# filter-10.net
KiCad netlist of a schematic drawn in Altium Designer
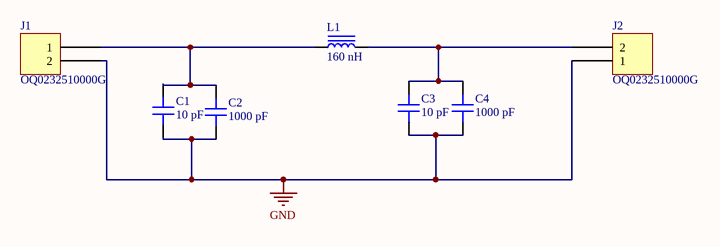
[diagram p0: filter-10.SchDoc]

(export (version "E")
  (design (tool "Eeschema 10.0.6"))
  (components
    (comp (ref "C1")
      (value "10 pF")
      (footprint "CAP 0603_1608")
      (description "CAP CER 10PF 100V C0G/NPO 0603")
      (fields (field (name "PART NUMBER") "AC0603JRNPO0BN100") (field (name "MANUFACTURER") "Yageo"))
      (libsource (lib "Celestial Altium Library - altium_library") (part "Capacitor"))
    )
    (comp (ref "C2")
      (value "1000 pF")
      (footprint "CAP 0603_1608")
      (description "CAP CER 1000PF 100V X7R 0603")
      (fields
        (field (name "PART NUMBER") "GCD188R72A102KA01D")
        (field (name "MANUFACTURER") "Murata Electronics")
      )
      (libsource (lib "Celestial Altium Library - altium_library") (part "Capacitor"))
    )
    (comp (ref "C3")
      (value "10 pF")
      (footprint "CAP 0603_1608")
      (description "CAP CER 10PF 100V C0G/NPO 0603")
      (fields (field (name "PART NUMBER") "AC0603JRNPO0BN100") (field (name "MANUFACTURER") "Yageo"))
      (libsource (lib "Celestial Altium Library - altium_library") (part "Capacitor"))
    )
    (comp (ref "C4")
      (value "1000 pF")
      (footprint "CAP 0603_1608")
      (description "CAP CER 1000PF 100V X7R 0603")
      (fields
        (field (name "PART NUMBER") "GCD188R72A102KA01D")
        (field (name "MANUFACTURER") "Murata Electronics")
      )
      (libsource (lib "Celestial Altium Library - altium_library") (part "Capacitor"))
    )
    (comp (ref "J1")
      (value "OQ0232510000G")
      (footprint "FCI 06-381-2PIN")
      (description "TERM BLOCK HDR 2POS 90DEG 3.81MM")
      (fields (field (name "MANUFACTURER") "Amphenol Anytek"))
      (libsource (lib "Celestial Altium Library - altium_library") (part "2 Pin"))
    )
    (comp (ref "J2")
      (value "OQ0232510000G")
      (footprint "FCI 06-381-2PIN")
      (description "TERM BLOCK HDR 2POS 90DEG 3.81MM")
      (fields (field (name "MANUFACTURER") "Amphenol Anytek"))
      (libsource (lib "") (part "2 Pin_1"))
    )
    (comp (ref "L1")
      (value "160 nH")
      (footprint "IND 0402_1005 RF WW")
      (description "FIXED IND 160NH 480MA 330MOHM SM")
      (fields
        (field (name "PART NUMBER") "LQW15CNR16J00D")
        (field (name "MANUFACTURER") "Murata Electronics")
      )
      (libsource (lib "Celestial Altium Library - altium_library") (part "Inductor"))
    )
  )
  (nets
    (net (code "1") (name "GND") (class "Default")
      (node (ref "C1") (pin "1") (pinfunction "1_1") (pintype "passive"))
      (node (ref "C2") (pin "2") (pinfunction "2_2") (pintype "passive"))
      (node (ref "C3") (pin "1") (pinfunction "1_1") (pintype "passive"))
      (node (ref "C4") (pin "2") (pinfunction "2_2") (pintype "passive"))
      (node (ref "J1") (pin "2") (pinfunction "2_2") (pintype "passive"))
      (node (ref "J2") (pin "1") (pinfunction "1_1") (pintype "passive"))
    )
    (net (code "2") (name "Net-(C1-Pad2)") (class "Default")
      (node (ref "C1") (pin "2") (pinfunction "2_2") (pintype "passive"))
      (node (ref "C2") (pin "1") (pinfunction "1_1") (pintype "passive"))
      (node (ref "J1") (pin "1") (pinfunction "1_1") (pintype "passive"))
      (node (ref "L1") (pin "1") (pinfunction "1_1") (pintype "passive"))
    )
    (net (code "3") (name "Net-(C3-Pad2)") (class "Default")
      (node (ref "C3") (pin "2") (pinfunction "2_2") (pintype "passive"))
      (node (ref "C4") (pin "1") (pinfunction "1_1") (pintype "passive"))
      (node (ref "J2") (pin "2") (pinfunction "2_2") (pintype "passive"))
      (node (ref "L1") (pin "2") (pinfunction "2_2") (pintype "passive"))
    )
  )
)
